# OpenMEA_Power_V002.net
KiCad netlist of a schematic drawn in Altium Designer
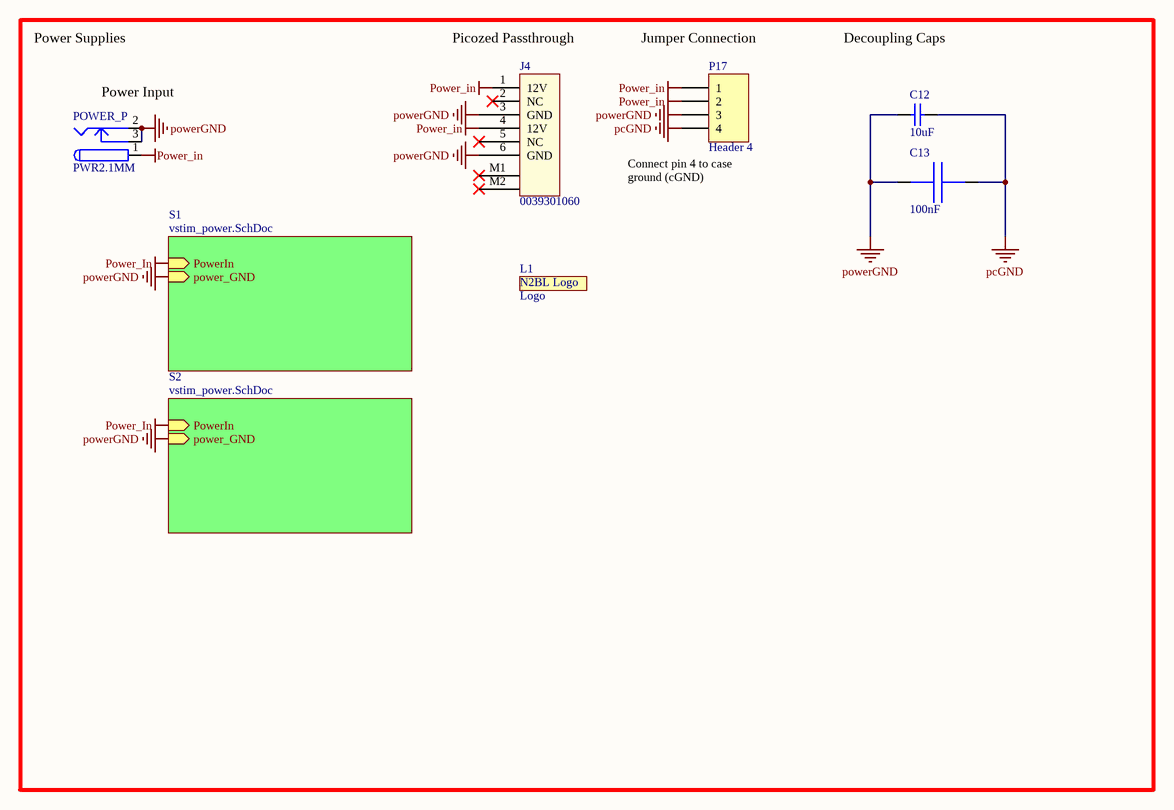
[diagram p0: OpenMEA_Power_V002.SchDoc]

(export (version "E")
  (design (tool "Eeschema 10.0.6"))
  (components
    (comp (ref "C12")
      (value "10uF")
      (footprint "Thesis_Testboard_V1I1:C0805")
      (description "CAP 10UF")
      (fields
        (field (name "MANUFACTURER") "Samsung Electro-Mechanics")
        (field (name "MANUFACTURER PART NUMBER") "CL21A106KAYNNNE")
      )
      (libsource (lib "standard_components") (part "C2012X5R1E106K085AC"))
    )
    (comp (ref "C13")
      (value "100nF")
      (footprint "rcl_smd_chip_ipc:rcl_0402i_1005m_most")
      (description "Capacitor Non-polarized American Symbol")
      (fields
        (field (name "MANUFACTURER") "Yageo")
        (field (name "MANURACTURER PART NUMBER") "CC0402KRX7R8BB104")
      )
      (libsource (lib "rcl_passives") (part "capacitor_npol_ame"))
    )
    (comp (ref "J4")
      (value "0039301060")
      (footprint "molex_pcb_headers:0039301060")
      (description "CONN HEADER R/A 6POS 4.2MM")
      (fields (field (name "MANUFACTURER") "Molex"))
      (libsource (lib "molex_pcb_headers") (part "0039301060"))
    )
    (comp (ref "L1")
      (value "Logo")
      (footprint "N2BL_LOGO")
      (libsource (lib "logo") (part "Neuron To Brain Lab Logo"))
    )
    (comp (ref "P17")
      (value "Header 4")
      (footprint "on_shore_rising_clamp:OSTVN04A150")
      (description "Header, 4-Pin")
      (fields
        (field (name "MANUFACTURER") "On Shore Technology Inc.")
        (field (name "MANUFACTURER PART NUMBER") "OSTVN04A150")
        (field (name "PUBLISHER") "Altium Limited")
      )
      (libsource (lib "standard_components") (part "Header 4"))
    )
    (comp (ref "POWER_P")
      (value "PWR2.1MM")
      (footprint "Thesis_Testboard_V1I1:POWER2.1MM")
      (description "PJ-002AH")
      (fields (field (name "MANUFACTURER") "CUI"))
      (libsource (lib "Thesis_Testboard_V1I1") (part "PWR2.1MM"))
    )
  )
  (nets
    (net (code "2") (name "Power_in") (class "Default")
      (node (ref "J4") (pin "1") (pinfunction "12V_1") (pintype "passive"))
      (node (ref "J4") (pin "4") (pinfunction "12V_4") (pintype "passive"))
      (node (ref "P17") (pin "1") (pinfunction "1_1") (pintype "passive"))
      (node (ref "P17") (pin "2") (pinfunction "2_2") (pintype "passive"))
      (node (ref "POWER_P") (pin "1") (pinfunction "1_1") (pintype "power_in"))
    )
    (net (code "3") (name "pcGND") (class "Default")
      (node (ref "C12") (pin "1") (pinfunction "1_1") (pintype "passive"))
      (node (ref "C13") (pin "1") (pinfunction "1_1") (pintype "passive"))
      (node (ref "P17") (pin "4") (pinfunction "4_4") (pintype "passive"))
    )
    (net (code "4") (name "powerGND") (class "Default")
      (node (ref "C12") (pin "2") (pinfunction "2_2") (pintype "passive"))
      (node (ref "C13") (pin "2") (pinfunction "2_2") (pintype "passive"))
      (node (ref "J4") (pin "3") (pinfunction "GND_3") (pintype "passive"))
      (node (ref "J4") (pin "6") (pinfunction "GND_6") (pintype "passive"))
      (node (ref "P17") (pin "3") (pinfunction "3_3") (pintype "passive"))
      (node (ref "POWER_P") (pin "2") (pintype "power_in"))
      (node (ref "POWER_P") (pin "3") (pinfunction "3_3") (pintype "power_in"))
    )
    (net (code "5") (name "unconnected-(J4-NC-Pad2)") (class "Default")
      (node (ref "J4") (pin "2") (pinfunction "NC_2") (pintype "passive+no_connect"))
    )
    (net (code "6") (name "unconnected-(J4-NC-Pad5)") (class "Default")
      (node (ref "J4") (pin "5") (pinfunction "NC_5") (pintype "passive+no_connect"))
    )
    (net (code "7") (name "unconnected-(J4-PadM1)") (class "Default")
      (node (ref "J4") (pin "M1") (pinfunction "M1_M1") (pintype "passive+no_connect"))
    )
    (net (code "8") (name "unconnected-(J4-PadM2)") (class "Default")
      (node (ref "J4") (pin "M2") (pinfunction "M2_M2") (pintype "passive+no_connect"))
    )
  )
)
